# power.net
KiCad netlist of a schematic drawn in EAGLE
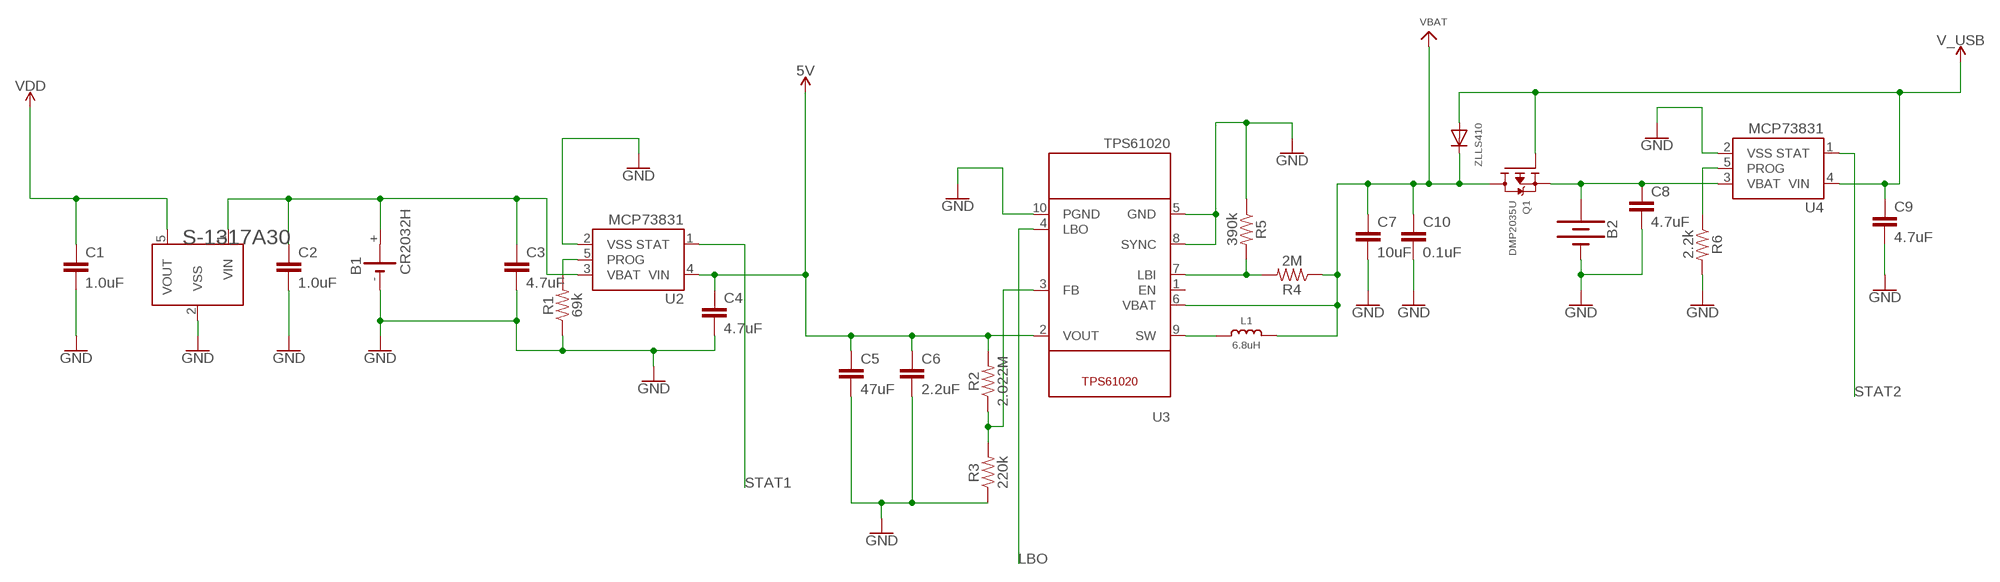
[diagram p0: schematic, sheet 1]

(export (version "E")
  (design (tool "Eeschema 10.0.6"))
  (components
    (comp (ref "B1")
      (value "CR2032H")
      (footprint "eagle-import:CR2032H")
      (libsource (lib "eagle-import") (part "CR2032H"))
    )
    (comp (ref "B2")
      (value "BATTERY-18650")
      (footprint "eagle-import:BATTERY_18650-HOLDER")
      (libsource (lib "eagle-import") (part "BATTERY-18650"))
    )
    (comp (ref "C1")
      (value "1.0uF")
      (footprint "eagle-import:0805")
      (libsource (lib "eagle-import") (part "1.0UF-0805-25V-(+80/-20%)"))
    )
    (comp (ref "C2")
      (value "1.0uF")
      (footprint "eagle-import:0805")
      (libsource (lib "eagle-import") (part "1.0UF-0805-25V-(+80/-20%)"))
    )
    (comp (ref "C3")
      (value "4.7uF")
      (footprint "eagle-import:0805")
      (libsource (lib "eagle-import") (part "1.0UF-0805-25V-(+80/-20%)"))
    )
    (comp (ref "C4")
      (value "4.7uF")
      (footprint "eagle-import:0805")
      (libsource (lib "eagle-import") (part "1.0UF-0805-25V-(+80/-20%)"))
    )
    (comp (ref "C5")
      (value "47uF")
      (footprint "eagle-import:0805")
      (libsource (lib "eagle-import") (part "1.0UF-0805-25V-(+80/-20%)"))
    )
    (comp (ref "C6")
      (value "2.2uF")
      (footprint "eagle-import:0805")
      (libsource (lib "eagle-import") (part "1.0UF-0805-25V-(+80/-20%)"))
    )
    (comp (ref "C7")
      (value "10uF")
      (footprint "eagle-import:0805")
      (libsource (lib "eagle-import") (part "1.0UF-0805-25V-(+80/-20%)"))
    )
    (comp (ref "C8")
      (value "4.7uF")
      (footprint "eagle-import:0805")
      (libsource (lib "eagle-import") (part "1.0UF-0805-25V-(+80/-20%)"))
    )
    (comp (ref "C9")
      (value "4.7uF")
      (footprint "eagle-import:0805")
      (libsource (lib "eagle-import") (part "1.0UF-0805-25V-(+80/-20%)"))
    )
    (comp (ref "C10")
      (value "0.1uF")
      (footprint "eagle-import:0805")
      (libsource (lib "eagle-import") (part "1.0UF-0805-25V-(+80/-20%)"))
    )
    (comp (ref "L1")
      (value "6.8uH")
      (footprint "eagle-import:INDUCTOR_5X5MM_TDK_VLC5045")
      (libsource (lib "eagle-import") (part "INDUCTORTDK_VLC5045"))
    )
    (comp (ref "Q1")
      (value "DMP2035U")
      (footprint "eagle-import:DMP")
      (libsource (lib "eagle-import") (part "DMP2035U"))
    )
    (comp (ref "R1")
      (value "69k")
      (footprint "eagle-import:0805")
      (libsource (lib "eagle-import") (part "RESISTOR0805"))
    )
    (comp (ref "R2")
      (value "2.022M")
      (footprint "eagle-import:0805")
      (libsource (lib "eagle-import") (part "RESISTOR0805"))
    )
    (comp (ref "R3")
      (value "220k")
      (footprint "eagle-import:0805")
      (libsource (lib "eagle-import") (part "RESISTOR0805"))
    )
    (comp (ref "R4")
      (value "2M")
      (footprint "eagle-import:0805")
      (libsource (lib "eagle-import") (part "RESISTOR0805"))
    )
    (comp (ref "R5")
      (value "390k")
      (footprint "eagle-import:0805")
      (libsource (lib "eagle-import") (part "RESISTOR0805"))
    )
    (comp (ref "R6")
      (value "2.2k")
      (footprint "eagle-import:0805")
      (libsource (lib "eagle-import") (part "RESISTOR0805"))
    )
    (comp (ref "S-1317A30")
      (value "S1317A30")
      (footprint "eagle-import:SOT23-5")
      (libsource (lib "eagle-import") (part "S1317A30"))
    )
    (comp (ref "U2")
      (value "MCP73831")
      (footprint "eagle-import:SOT23-5")
      (libsource (lib "eagle-import") (part "MCP73831"))
    )
    (comp (ref "U3")
      (value "TPS61020")
      (footprint "eagle-import:S-PDSO-N10")
      (libsource (lib "eagle-import") (part "TPS61020"))
    )
    (comp (ref "U4")
      (value "MCP73831")
      (footprint "eagle-import:SOT23-5")
      (libsource (lib "eagle-import") (part "MCP73831"))
    )
    (comp (ref "ZLLS410")
      (value "DIODESOD-323")
      (footprint "eagle-import:SOD-323")
      (libsource (lib "eagle-import") (part "DIODESOD-323"))
    )
  )
  (nets
    (net (code "1") (name "/LBO") (class "Default")
      (node (ref "U3") (pin "4") (pinfunction "LBO_4") (pintype "output"))
    )
    (net (code "2") (name "/STAT1") (class "Default")
      (node (ref "U2") (pin "1") (pinfunction "STAT_1") (pintype "output"))
    )
    (net (code "3") (name "/STAT2") (class "Default")
      (node (ref "U4") (pin "1") (pinfunction "STAT_1") (pintype "output"))
    )
    (net (code "4") (name "5V") (class "Default")
      (node (ref "C4") (pin "1") (pinfunction "1_1") (pintype "passive"))
      (node (ref "C5") (pin "1") (pinfunction "1_1") (pintype "passive"))
      (node (ref "C6") (pin "1") (pinfunction "1_1") (pintype "passive"))
      (node (ref "R2") (pin "2") (pinfunction "2_2") (pintype "passive"))
      (node (ref "U2") (pin "4") (pinfunction "VIN_4") (pintype "power_in"))
      (node (ref "U3") (pin "2") (pinfunction "VOUT_2") (pintype "power_in"))
    )
    (net (code "5") (name "GND") (class "Default")
      (node (ref "B1") (pin "-") (pinfunction "-_-") (pintype "passive"))
      (node (ref "B2") (pin "GND@1") (pinfunction "-_GND@1") (pintype "power_in"))
      (node (ref "C1") (pin "2") (pinfunction "2_2") (pintype "passive"))
      (node (ref "C10") (pin "2") (pinfunction "2_2") (pintype "passive"))
      (node (ref "C2") (pin "2") (pinfunction "2_2") (pintype "passive"))
      (node (ref "C3") (pin "2") (pinfunction "2_2") (pintype "passive"))
      (node (ref "C4") (pin "2") (pinfunction "2_2") (pintype "passive"))
      (node (ref "C5") (pin "2") (pinfunction "2_2") (pintype "passive"))
      (node (ref "C6") (pin "2") (pinfunction "2_2") (pintype "passive"))
      (node (ref "C7") (pin "2") (pinfunction "2_2") (pintype "passive"))
      (node (ref "C8") (pin "2") (pinfunction "2_2") (pintype "passive"))
      (node (ref "C9") (pin "2") (pinfunction "2_2") (pintype "passive"))
      (node (ref "R1") (pin "1") (pinfunction "1_1") (pintype "passive"))
      (node (ref "R3") (pin "1") (pinfunction "1_1") (pintype "passive"))
      (node (ref "R5") (pin "1") (pinfunction "1_1") (pintype "passive"))
      (node (ref "R6") (pin "2") (pinfunction "2_2") (pintype "passive"))
      (node (ref "S-1317A30") (pin "2") (pinfunction "VSS_2") (pintype "bidirectional"))
      (node (ref "U2") (pin "2") (pinfunction "VSS_2") (pintype "power_in"))
      (node (ref "U3") (pin "10") (pinfunction "PGND_10") (pintype "power_in"))
      (node (ref "U3") (pin "5") (pinfunction "GND_5") (pintype "power_in"))
      (node (ref "U3") (pin "8") (pinfunction "SYNC_8") (pintype "input"))
      (node (ref "U4") (pin "2") (pinfunction "VSS_2") (pintype "power_in"))
    )
    (net (code "6") (name "Net-(B2-+)") (class "Default")
      (node (ref "B2") (pin "PWR@1") (pinfunction "+_PWR@1") (pintype "power_in"))
      (node (ref "C8") (pin "1") (pinfunction "1_1") (pintype "passive"))
      (node (ref "Q1") (pin "2") (pinfunction "S_2") (pintype "passive"))
      (node (ref "U4") (pin "3") (pinfunction "VBAT_3") (pintype "power_in"))
    )
    (net (code "7") (name "Net-(L1-1)") (class "Default")
      (node (ref "L1") (pin "P$1") (pinfunction "1_P$1") (pintype "passive"))
      (node (ref "U3") (pin "9") (pinfunction "SW_9") (pintype "input"))
    )
    (net (code "8") (name "Net-(S-1317A30-VIN)") (class "Default")
      (node (ref "B1") (pin "+") (pinfunction "+_+") (pintype "passive"))
      (node (ref "C2") (pin "1") (pinfunction "1_1") (pintype "passive"))
      (node (ref "C3") (pin "1") (pinfunction "1_1") (pintype "passive"))
      (node (ref "S-1317A30") (pin "1") (pinfunction "VIN_1") (pintype "bidirectional"))
      (node (ref "U2") (pin "3") (pinfunction "VBAT_3") (pintype "power_in"))
    )
    (net (code "9") (name "Net-(U2-PROG)") (class "Default")
      (node (ref "R1") (pin "2") (pinfunction "2_2") (pintype "passive"))
      (node (ref "U2") (pin "5") (pinfunction "PROG_5") (pintype "input"))
    )
    (net (code "10") (name "Net-(U3-FB)") (class "Default")
      (node (ref "R2") (pin "1") (pinfunction "1_1") (pintype "passive"))
      (node (ref "R3") (pin "2") (pinfunction "2_2") (pintype "passive"))
      (node (ref "U3") (pin "3") (pinfunction "FB_3") (pintype "input"))
    )
    (net (code "11") (name "Net-(U3-LBI)") (class "Default")
      (node (ref "R4") (pin "2") (pinfunction "2_2") (pintype "passive"))
      (node (ref "R5") (pin "2") (pinfunction "2_2") (pintype "passive"))
      (node (ref "U3") (pin "7") (pinfunction "LBI_7") (pintype "input"))
    )
    (net (code "12") (name "Net-(U4-PROG)") (class "Default")
      (node (ref "R6") (pin "1") (pinfunction "1_1") (pintype "passive"))
      (node (ref "U4") (pin "5") (pinfunction "PROG_5") (pintype "input"))
    )
    (net (code "13") (name "VBAT") (class "Default")
      (node (ref "C10") (pin "1") (pinfunction "1_1") (pintype "passive"))
      (node (ref "C7") (pin "1") (pinfunction "1_1") (pintype "passive"))
      (node (ref "L1") (pin "P$2") (pinfunction "2_P$2") (pintype "passive"))
      (node (ref "Q1") (pin "3") (pinfunction "D_3") (pintype "passive"))
      (node (ref "R4") (pin "1") (pinfunction "1_1") (pintype "passive"))
      (node (ref "U3") (pin "6") (pinfunction "VBAT_6") (pintype "input"))
      (node (ref "ZLLS410") (pin "C") (pinfunction "C_C") (pintype "passive"))
    )
    (net (code "14") (name "VDD") (class "Default")
      (node (ref "C1") (pin "1") (pinfunction "1_1") (pintype "passive"))
      (node (ref "S-1317A30") (pin "5") (pinfunction "VOUT_5") (pintype "bidirectional"))
    )
    (net (code "15") (name "V_USB") (class "Default")
      (node (ref "C9") (pin "1") (pinfunction "1_1") (pintype "passive"))
      (node (ref "Q1") (pin "1") (pinfunction "G_1") (pintype "passive"))
      (node (ref "U4") (pin "4") (pinfunction "VIN_4") (pintype "power_in"))
      (node (ref "ZLLS410") (pin "A") (pinfunction "A_A") (pintype "passive"))
    )
    (net (code "16") (name "unconnected-(B1-+-Pad+@1)") (class "Default")
      (node (ref "B1") (pin "+@1") (pinfunction "+_+@1") (pintype "passive"))
    )
    (net (code "17") (name "unconnected-(U3-EN-Pad1)") (class "Default")
      (node (ref "U3") (pin "1") (pinfunction "EN_1") (pintype "input"))
    )
  )
)
